# LPC_ERT_30_v3_51_RE.net
KiCad netlist of a schematic drawn in EAGLE
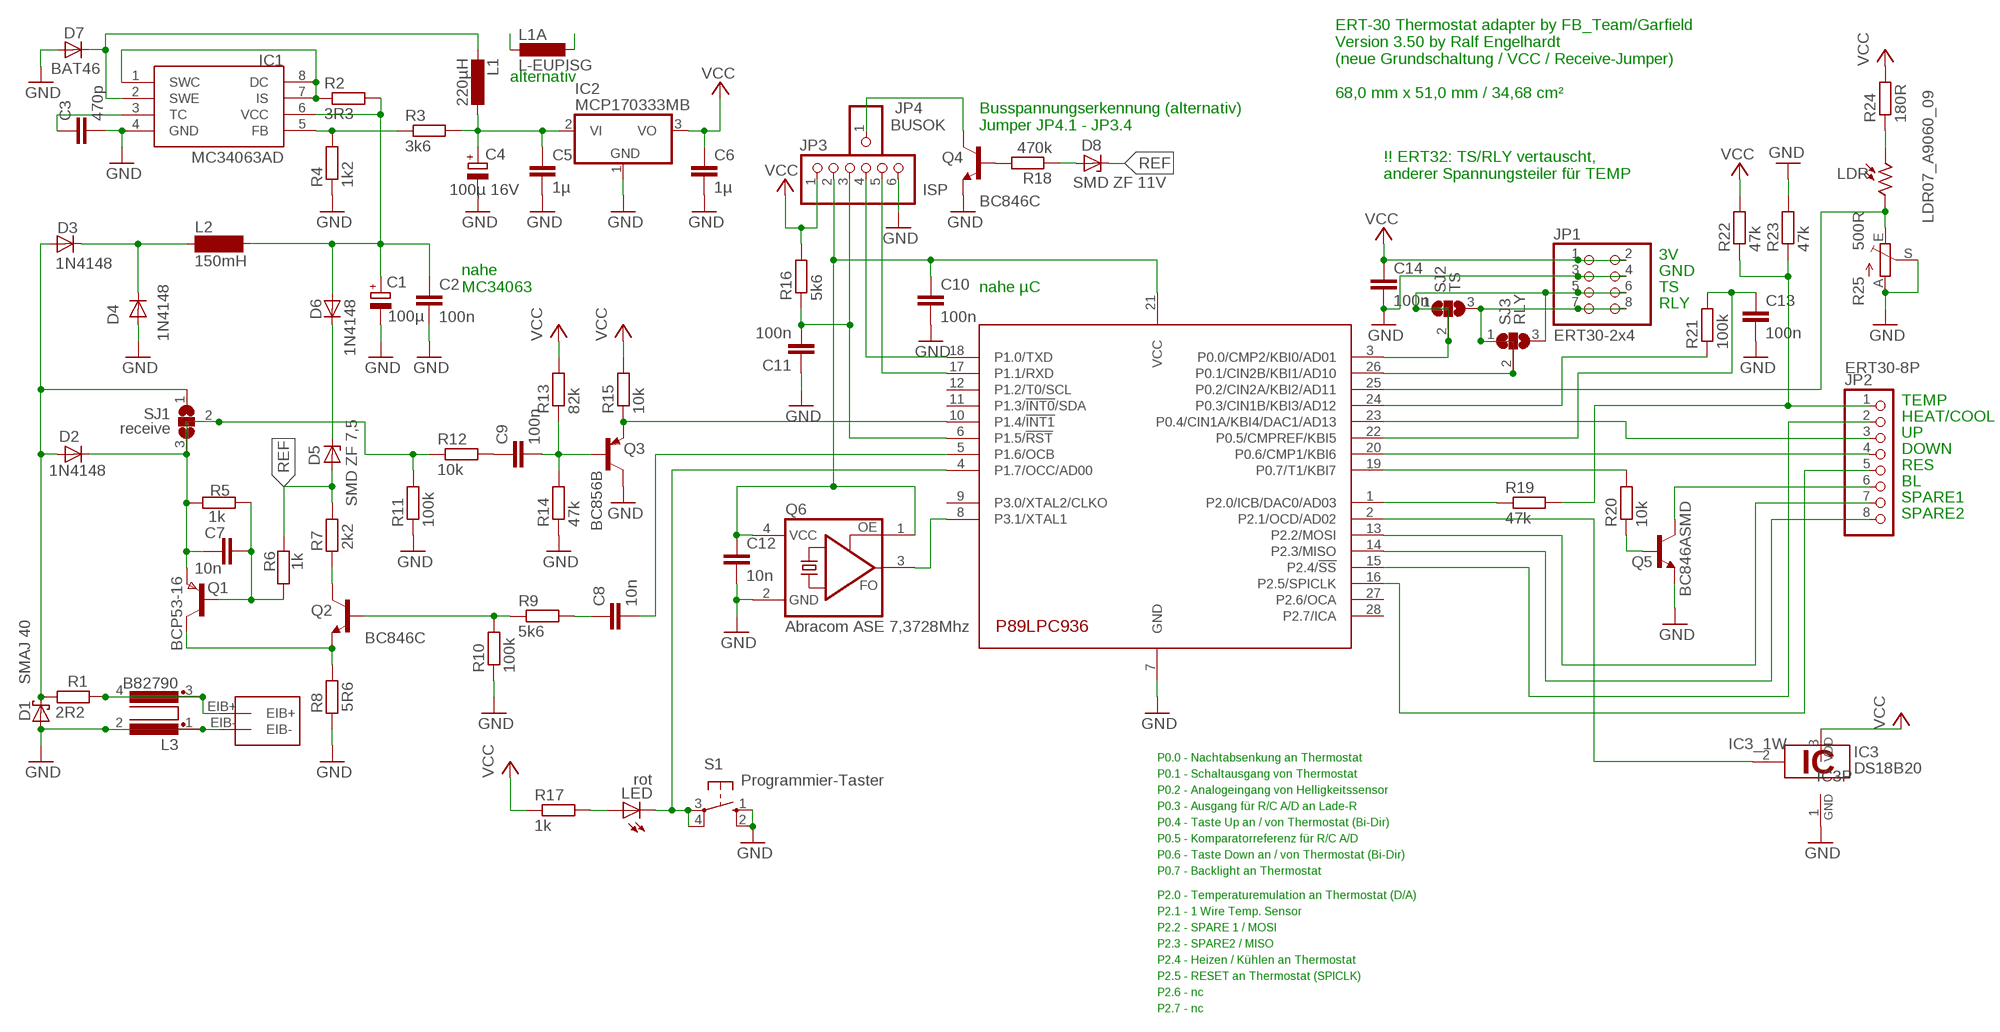
[diagram p0: schematic, sheet 1]

(export (version "E")
  (design (tool "Eeschema 10.0.6"))
  (components
    (comp (ref "C1")
      (value "100µ")
      (footprint "eagle-import:153CLV-0605")
      (libsource (lib "eagle-import") (part "CPOL-EU153CLV-0605"))
    )
    (comp (ref "C2")
      (value "100n")
      (footprint "eagle-import:C1206")
      (libsource (lib "eagle-import") (part "C-EUC1206"))
    )
    (comp (ref "C3")
      (value "470p")
      (footprint "eagle-import:C1206")
      (libsource (lib "eagle-import") (part "C-EUC1206"))
    )
    (comp (ref "C4")
      (value "100µ 16V")
      (footprint "eagle-import:153CLV-0605")
      (libsource (lib "eagle-import") (part "CPOL-EU153CLV-0605"))
    )
    (comp (ref "C5")
      (value "1µ")
      (footprint "eagle-import:C1206")
      (libsource (lib "eagle-import") (part "C-EUC1206"))
    )
    (comp (ref "C6")
      (value "1µ")
      (footprint "eagle-import:C1206")
      (libsource (lib "eagle-import") (part "C-EUC1206"))
    )
    (comp (ref "C7")
      (value "10n")
      (footprint "eagle-import:C1206")
      (libsource (lib "eagle-import") (part "C-EUC1206"))
    )
    (comp (ref "C8")
      (value "10n")
      (footprint "eagle-import:C1206")
      (libsource (lib "eagle-import") (part "C-EUC1206"))
    )
    (comp (ref "C9")
      (value "100n")
      (footprint "eagle-import:C1206")
      (libsource (lib "eagle-import") (part "C-EUC1206"))
    )
    (comp (ref "C10")
      (value "100n")
      (footprint "eagle-import:C1206")
      (libsource (lib "eagle-import") (part "C-EUC1206"))
    )
    (comp (ref "C11")
      (value "100n")
      (footprint "eagle-import:C1206")
      (libsource (lib "eagle-import") (part "C-EUC1206"))
    )
    (comp (ref "C12")
      (value "10n")
      (footprint "eagle-import:C1206")
      (libsource (lib "eagle-import") (part "C-EUC1206"))
    )
    (comp (ref "C13")
      (value "100n")
      (footprint "eagle-import:C1206")
      (libsource (lib "eagle-import") (part "C-EUC1206"))
    )
    (comp (ref "C14")
      (value "100n")
      (footprint "eagle-import:C1206")
      (libsource (lib "eagle-import") (part "C-EUC1206"))
    )
    (comp (ref "D1")
      (value "SMAJ 40")
      (footprint "eagle-import:SMB")
      (libsource (lib "eagle-import") (part "MBRS130LT3"))
    )
    (comp (ref "D2")
      (value "1N4148")
      (footprint "eagle-import:MINIMELF")
      (libsource (lib "eagle-import") (part "DIODE-MINIMELF"))
    )
    (comp (ref "D3")
      (value "1N4148")
      (footprint "eagle-import:MINIMELF")
      (libsource (lib "eagle-import") (part "DIODE-MINIMELF"))
    )
    (comp (ref "D4")
      (value "1N4148")
      (footprint "eagle-import:MINIMELF")
      (libsource (lib "eagle-import") (part "DIODE-MINIMELF"))
    )
    (comp (ref "D5")
      (value "SMD ZF 7,5")
      (footprint "eagle-import:MINIMELF")
      (libsource (lib "eagle-import") (part "ZENER-DIODESMD_ZF_XX"))
    )
    (comp (ref "D6")
      (value "1N4148")
      (footprint "eagle-import:MINIMELF")
      (libsource (lib "eagle-import") (part "DIODE-MINIMELF"))
    )
    (comp (ref "D7")
      (value "BAT46")
      (footprint "eagle-import:MINIMELF")
      (libsource (lib "eagle-import") (part "DIODE-MINIMELF"))
    )
    (comp (ref "D8")
      (value "SMD ZF 11V")
      (footprint "eagle-import:MINIMELF")
      (libsource (lib "eagle-import") (part "ZENER-DIODESMD_ZF_XX"))
    )
    (comp (ref "IC1")
      (value "MC34063AD")
      (footprint "eagle-import:SOIC8")
      (libsource (lib "eagle-import") (part "MC34063AD"))
    )
    (comp (ref "IC2")
      (value "MCP170333MB")
      (footprint "eagle-import:SOT89")
      (libsource (lib "eagle-import") (part "MCP1703MB33"))
    )
    (comp (ref "IC3")
      (value "DS18B20")
      (footprint "eagle-import:TO92-")
      (libsource (lib "eagle-import") (part "DS18B20"))
    )
    (comp (ref "JP1")
      (value "ERT30-2x4")
      (footprint "eagle-import:2X04")
      (libsource (lib "eagle-import") (part "PINHD-2X4"))
    )
    (comp (ref "JP2")
      (value "ERT30-8P")
      (footprint "eagle-import:PS-G-8")
      (libsource (lib "eagle-import") (part "PS-HEADER-8GERADE"))
    )
    (comp (ref "JP3")
      (value "ISP")
      (footprint "eagle-import:1X06_SELFBUS")
      (libsource (lib "eagle-import") (part "PINHD-1X6SELFBUS"))
    )
    (comp (ref "JP4")
      (value "BUSOK")
      (footprint "eagle-import:1X01_SELFBUS")
      (libsource (lib "eagle-import") (part "PINHD-1X1SELFBUS"))
    )
    (comp (ref "L1")
      (value "220µH")
      (footprint "eagle-import:PIS24XX")
      (libsource (lib "eagle-import") (part "L-EUPIS24XX"))
    )
    (comp (ref "L1A")
      (value "L-EUPISG")
      (footprint "eagle-import:PISG")
      (libsource (lib "eagle-import") (part "L-EUPISG"))
    )
    (comp (ref "L2")
      (value "150mH")
      (footprint "eagle-import:SD12_1000")
      (libsource (lib "eagle-import") (part "SD12-1000"))
    )
    (comp (ref "L3")
      (value "B82790")
      (footprint "eagle-import:B82790")
      (libsource (lib "eagle-import") (part "B82790"))
    )
    (comp (ref "LDR")
      (value "LDR07_A9060_09")
      (footprint "eagle-import:A90XX")
      (libsource (lib "eagle-import") (part "LDR07"))
    )
    (comp (ref "LED")
      (value "rot")
      (footprint "eagle-import:CHIPLED_1206")
      (libsource (lib "eagle-import") (part "LEDCHIPLED_1206"))
    )
    (comp (ref "LPC")
      (value "P98LPC936 TSOP28")
      (footprint "eagle-import:TSSOP28")
      (libsource (lib "eagle-import") (part "P89LPC936_SMDTSSOP28"))
    )
    (comp (ref "Q1")
      (value "BCP53-16")
      (footprint "eagle-import:SOT223")
      (fields (field (name "MPN") "DJT4030P-13"))
      (libsource (lib "eagle-import") (part "PNPSOT223"))
    )
    (comp (ref "Q2")
      (value "BC846C")
      (footprint "eagle-import:SOT23")
      (libsource (lib "eagle-import") (part "BC846"))
    )
    (comp (ref "Q3")
      (value "BC856B")
      (footprint "eagle-import:SOT23-BEC")
      (libsource (lib "eagle-import") (part "-PNP-SOT23-BECBC856B"))
    )
    (comp (ref "Q4")
      (value "BC846C")
      (footprint "eagle-import:SOT23")
      (libsource (lib "eagle-import") (part "BC846"))
    )
    (comp (ref "Q5")
      (value "BC846ASMD")
      (footprint "eagle-import:SOT23")
      (libsource (lib "eagle-import") (part "BC846SMDA"))
    )
    (comp (ref "Q6")
      (value "Abracom ASE 7,3728Mhz")
      (footprint "eagle-import:ASFL3")
      (libsource (lib "eagle-import") (part "ASFASFL3"))
    )
    (comp (ref "R1")
      (value "2R2")
      (footprint "eagle-import:R1206")
      (libsource (lib "eagle-import") (part "R-EU_R1206"))
    )
    (comp (ref "R2")
      (value "3R3")
      (footprint "eagle-import:R1206")
      (libsource (lib "eagle-import") (part "R-EU_R1206"))
    )
    (comp (ref "R3")
      (value "3k6")
      (footprint "eagle-import:R1206")
      (libsource (lib "eagle-import") (part "R-EU_R1206"))
    )
    (comp (ref "R4")
      (value "1k2")
      (footprint "eagle-import:R1206")
      (libsource (lib "eagle-import") (part "R-EU_R1206"))
    )
    (comp (ref "R5")
      (value "1k")
      (footprint "eagle-import:R1206")
      (libsource (lib "eagle-import") (part "R-EU_R1206"))
    )
    (comp (ref "R6")
      (value "1k")
      (footprint "eagle-import:R1206")
      (libsource (lib "eagle-import") (part "R-EU_R1206"))
    )
    (comp (ref "R7")
      (value "2k2")
      (footprint "eagle-import:R1206")
      (libsource (lib "eagle-import") (part "R-EU_R1206"))
    )
    (comp (ref "R8")
      (value "5R6")
      (footprint "eagle-import:R1206")
      (libsource (lib "eagle-import") (part "R-EU_R1206"))
    )
    (comp (ref "R9")
      (value "5k6")
      (footprint "eagle-import:R1206")
      (libsource (lib "eagle-import") (part "R-EU_R1206"))
    )
    (comp (ref "R10")
      (value "100k")
      (footprint "eagle-import:R1206")
      (libsource (lib "eagle-import") (part "R-EU_R1206"))
    )
    (comp (ref "R11")
      (value "100k")
      (footprint "eagle-import:R1206")
      (libsource (lib "eagle-import") (part "R-EU_R1206"))
    )
    (comp (ref "R12")
      (value "10k")
      (footprint "eagle-import:R1206")
      (libsource (lib "eagle-import") (part "R-EU_R1206"))
    )
    (comp (ref "R13")
      (value "82k")
      (footprint "eagle-import:R1206")
      (libsource (lib "eagle-import") (part "R-EU_R1206"))
    )
    (comp (ref "R14")
      (value "47k")
      (footprint "eagle-import:R1206")
      (libsource (lib "eagle-import") (part "R-EU_R1206"))
    )
    (comp (ref "R15")
      (value "10k")
      (footprint "eagle-import:R1206")
      (libsource (lib "eagle-import") (part "R-EU_R1206"))
    )
    (comp (ref "R16")
      (value "5k6")
      (footprint "eagle-import:R1206")
      (libsource (lib "eagle-import") (part "R-EU_R1206"))
    )
    (comp (ref "R17")
      (value "1k")
      (footprint "eagle-import:R1206")
      (libsource (lib "eagle-import") (part "R-EU_R1206"))
    )
    (comp (ref "R18")
      (value "470k")
      (footprint "eagle-import:R1206")
      (libsource (lib "eagle-import") (part "R-EU_R1206"))
    )
    (comp (ref "R19")
      (value "47k")
      (footprint "eagle-import:R1206")
      (libsource (lib "eagle-import") (part "R-EU_R1206"))
    )
    (comp (ref "R20")
      (value "10k")
      (footprint "eagle-import:R1206")
      (libsource (lib "eagle-import") (part "R-EU_R1206"))
    )
    (comp (ref "R21")
      (value "100k")
      (footprint "eagle-import:R1206")
      (libsource (lib "eagle-import") (part "R-EU_R1206"))
    )
    (comp (ref "R22")
      (value "47k")
      (footprint "eagle-import:R1206")
      (libsource (lib "eagle-import") (part "R-EU_R1206"))
    )
    (comp (ref "R23")
      (value "47k")
      (footprint "eagle-import:R1206")
      (libsource (lib "eagle-import") (part "R-EU_R1206"))
    )
    (comp (ref "R24")
      (value "180R")
      (footprint "eagle-import:R1206")
      (libsource (lib "eagle-import") (part "R-EU_R1206"))
    )
    (comp (ref "R25")
      (value "500R")
      (footprint "eagle-import:CA6H")
      (libsource (lib "eagle-import") (part "TRIM_EU-CA6H"))
    )
    (comp (ref "S1")
      (value "Programmier-Taster")
      (footprint "eagle-import:B3F-10XX")
      (fields (field (name "MPN") "B3F-1000"))
      (libsource (lib "eagle-import") (part "10-XX"))
    )
    (comp (ref "SJ1")
      (value "receive")
      (footprint "eagle-import:SJ_2")
      (libsource (lib "eagle-import") (part "SJ2W"))
    )
    (comp (ref "SJ2")
      (value "TS")
      (footprint "eagle-import:SJ_2")
      (libsource (lib "eagle-import") (part "SJ2W"))
    )
    (comp (ref "SJ3")
      (value "RLY")
      (footprint "eagle-import:SJ_2")
      (libsource (lib "eagle-import") (part "SJ2W"))
    )
    (comp (ref "U$5")
      (value "EIB-CON")
      (footprint "eagle-import:EIB-CON")
      (libsource (lib "eagle-import") (part "EIB-CON"))
    )
  )
  (nets
    (net (code "1") (name "/+5V") (class "Default")
      (node (ref "C4") (pin "+") (pinfunction "+_+") (pintype "passive"))
      (node (ref "C5") (pin "1") (pinfunction "1_1") (pintype "passive"))
      (node (ref "IC2") (pin "2") (pinfunction "VI_2") (pintype "input"))
      (node (ref "IC2") (pin "2@1") (pinfunction "VI1_2@1") (pintype "input"))
      (node (ref "L1") (pin "2") (pinfunction "1_2") (pintype "passive"))
      (node (ref "L1A") (pin "2") (pinfunction "2_2") (pintype "passive"))
      (node (ref "R3") (pin "2") (pinfunction "2_2") (pintype "passive"))
    )
    (net (code "2") (name "/SWE") (class "Default")
      (node (ref "D7") (pin "C") (pinfunction "C_C") (pintype "passive"))
      (node (ref "IC1") (pin "2") (pinfunction "SWE_2") (pintype "passive"))
      (node (ref "L1") (pin "1") (pinfunction "2_1") (pintype "passive"))
      (node (ref "L1A") (pin "1") (pinfunction "1_1") (pintype "passive"))
    )
    (net (code "3") (name "GND") (class "Default")
      (node (ref "C1") (pin "-") (pinfunction "-_-") (pintype "passive"))
      (node (ref "C10") (pin "2") (pinfunction "2_2") (pintype "passive"))
      (node (ref "C11") (pin "1") (pinfunction "1_1") (pintype "passive"))
      (node (ref "C12") (pin "2") (pinfunction "2_2") (pintype "passive"))
      (node (ref "C13") (pin "2") (pinfunction "2_2") (pintype "passive"))
      (node (ref "C14") (pin "2") (pinfunction "2_2") (pintype "passive"))
      (node (ref "C2") (pin "2") (pinfunction "2_2") (pintype "passive"))
      (node (ref "C3") (pin "2") (pinfunction "2_2") (pintype "passive"))
      (node (ref "C4") (pin "-") (pinfunction "-_-") (pintype "passive"))
      (node (ref "C5") (pin "2") (pinfunction "2_2") (pintype "passive"))
      (node (ref "C6") (pin "2") (pinfunction "2_2") (pintype "passive"))
      (node (ref "D1") (pin "A") (pinfunction "A_A") (pintype "passive"))
      (node (ref "D4") (pin "A") (pinfunction "A_A") (pintype "passive"))
      (node (ref "D7") (pin "A") (pinfunction "A_A") (pintype "passive"))
      (node (ref "IC1") (pin "4") (pinfunction "GND_4") (pintype "passive"))
      (node (ref "IC2") (pin "1") (pinfunction "GND_1") (pintype "passive"))
      (node (ref "IC3") (pin "1") (pinfunction "GND_1") (pintype "power_in"))
      (node (ref "JP1") (pin "3") (pinfunction "3_3") (pintype "passive"))
      (node (ref "JP1") (pin "4") (pinfunction "4_4") (pintype "passive"))
      (node (ref "JP3") (pin "6") (pinfunction "6_6") (pintype "passive"))
      (node (ref "L3") (pin "1") (pinfunction "1_1") (pintype "passive"))
      (node (ref "L3") (pin "2") (pinfunction "2_2") (pintype "passive"))
      (node (ref "LPC") (pin "7") (pinfunction "GND_7") (pintype "bidirectional"))
      (node (ref "Q3") (pin "C") (pinfunction "C_C") (pintype "passive"))
      (node (ref "Q4") (pin "2") (pinfunction "E_2") (pintype "passive"))
      (node (ref "Q5") (pin "2") (pinfunction "E_2") (pintype "passive"))
      (node (ref "Q6") (pin "2") (pinfunction "GND_2") (pintype "power_in"))
      (node (ref "R10") (pin "1") (pinfunction "1_1") (pintype "passive"))
      (node (ref "R11") (pin "1") (pinfunction "1_1") (pintype "passive"))
      (node (ref "R14") (pin "1") (pinfunction "1_1") (pintype "passive"))
      (node (ref "R23") (pin "2") (pinfunction "2_2") (pintype "passive"))
      (node (ref "R25") (pin "A") (pinfunction "A_A") (pintype "passive"))
      (node (ref "R25") (pin "S") (pinfunction "S_S") (pintype "passive"))
      (node (ref "R4") (pin "1") (pinfunction "1_1") (pintype "passive"))
      (node (ref "R8") (pin "1") (pinfunction "1_1") (pintype "passive"))
      (node (ref "S1") (pin "1") (pinfunction "S_1") (pintype "passive"))
      (node (ref "S1") (pin "2") (pinfunction "S1_2") (pintype "passive"))
      (node (ref "U$5") (pin "EIB-") (pinfunction "EIB-_EIB-") (pintype "bidirectional"))
    )
    (net (code "4") (name "Net-(C8-Pad1)") (class "Default")
      (node (ref "C8") (pin "1") (pinfunction "1_1") (pintype "passive"))
      (node (ref "R9") (pin "2") (pinfunction "2_2") (pintype "passive"))
    )
    (net (code "5") (name "Net-(C9-Pad1)") (class "Default")
      (node (ref "C9") (pin "1") (pinfunction "1_1") (pintype "passive"))
      (node (ref "R12") (pin "2") (pinfunction "2_2") (pintype "passive"))
    )
    (net (code "6") (name "Net-(C9-Pad2)") (class "Default")
      (node (ref "C9") (pin "2") (pinfunction "2_2") (pintype "passive"))
      (node (ref "Q3") (pin "B") (pinfunction "B_B") (pintype "passive"))
      (node (ref "R13") (pin "1") (pinfunction "1_1") (pintype "passive"))
      (node (ref "R14") (pin "2") (pinfunction "2_2") (pintype "passive"))
    )
    (net (code "7") (name "Net-(D1-PadC)") (class "Default")
      (node (ref "D1") (pin "C") (pinfunction "C_C") (pintype "passive"))
      (node (ref "D2") (pin "A") (pinfunction "A_A") (pintype "passive"))
      (node (ref "D3") (pin "A") (pinfunction "A_A") (pintype "passive"))
      (node (ref "R1") (pin "2") (pinfunction "2_2") (pintype "passive"))
      (node (ref "SJ1") (pin "1") (pinfunction "1_1") (pintype "passive"))
    )
    (net (code "8") (name "Net-(D3-PadC)") (class "Default")
      (node (ref "D3") (pin "C") (pinfunction "C_C") (pintype "passive"))
      (node (ref "D4") (pin "C") (pinfunction "C_C") (pintype "passive"))
      (node (ref "L2") (pin "1") (pinfunction "1_1") (pintype "passive"))
    )
    (net (code "9") (name "Net-(D5-PadC)") (class "Default")
      (node (ref "D5") (pin "C") (pinfunction "C_C") (pintype "passive"))
      (node (ref "D6") (pin "C") (pinfunction "C_C") (pintype "passive"))
    )
    (net (code "10") (name "Net-(D8-PadA)") (class "Default")
      (node (ref "D8") (pin "A") (pinfunction "A_A") (pintype "passive"))
      (node (ref "R18") (pin "1") (pinfunction "1_1") (pintype "passive"))
    )
    (net (code "11") (name "Net-(IC1-DC)") (class "Default")
      (node (ref "IC1") (pin "1") (pinfunction "SWC_1") (pintype "passive"))
      (node (ref "IC1") (pin "7") (pinfunction "IS_7") (pintype "passive"))
      (node (ref "IC1") (pin "8") (pinfunction "DC_8") (pintype "passive"))
      (node (ref "R2") (pin "1") (pinfunction "1_1") (pintype "passive"))
    )
    (net (code "12") (name "Net-(IC1-FB)") (class "Default")
      (node (ref "IC1") (pin "5") (pinfunction "FB_5") (pintype "passive"))
      (node (ref "R3") (pin "1") (pinfunction "1_1") (pintype "passive"))
      (node (ref "R4") (pin "2") (pinfunction "2_2") (pintype "passive"))
    )
    (net (code "13") (name "Net-(IC1-TC)") (class "Default")
      (node (ref "C3") (pin "1") (pinfunction "1_1") (pintype "passive"))
      (node (ref "IC1") (pin "3") (pinfunction "TC_3") (pintype "passive"))
    )
    (net (code "14") (name "Net-(IC1-VCC)") (class "Default")
      (node (ref "C1") (pin "+") (pinfunction "+_+") (pintype "passive"))
      (node (ref "C2") (pin "1") (pinfunction "1_1") (pintype "passive"))
      (node (ref "D6") (pin "A") (pinfunction "A_A") (pintype "passive"))
      (node (ref "IC1") (pin "6") (pinfunction "VCC_6") (pintype "passive"))
      (node (ref "L2") (pin "2") (pinfunction "2_2") (pintype "passive"))
      (node (ref "R2") (pin "2") (pinfunction "2_2") (pintype "passive"))
    )
    (net (code "15") (name "Net-(IC3C-1W)") (class "Default")
      (node (ref "IC3") (pin "2") (pinfunction "1W_2") (pintype "power_in"))
      (node (ref "LPC") (pin "2") (pinfunction "P2.1/OCD/AD02_2") (pintype "bidirectional"))
    )
    (net (code "16") (name "Net-(JP2-Pad1)") (class "Default")
      (node (ref "JP2") (pin "1") (pinfunction "1_1") (pintype "passive"))
      (node (ref "R19") (pin "2") (pinfunction "2_2") (pintype "passive"))
      (node (ref "R22") (pin "1") (pinfunction "1_1") (pintype "passive"))
      (node (ref "R23") (pin "1") (pinfunction "1_1") (pintype "passive"))
    )
    (net (code "17") (name "Net-(L3-Pad3)") (class "Default")
      (node (ref "L3") (pin "3") (pinfunction "3_3") (pintype "passive"))
      (node (ref "L3") (pin "4") (pinfunction "4_4") (pintype "passive"))
      (node (ref "R1") (pin "1") (pinfunction "1_1") (pintype "passive"))
      (node (ref "U$5") (pin "EIB+") (pinfunction "EIB+_EIB+") (pintype "bidirectional"))
    )
    (net (code "18") (name "Net-(LDR-1)") (class "Default")
      (node (ref "LDR") (pin "P$1") (pinfunction "1_P$1") (pintype "passive"))
      (node (ref "R24") (pin "1") (pinfunction "1_1") (pintype "passive"))
    )
    (net (code "19") (name "Net-(LDR-2)") (class "Default")
      (node (ref "LDR") (pin "P$2") (pinfunction "2_P$2") (pintype "passive"))
      (node (ref "LPC") (pin "25") (pinfunction "P0.2/CIN2A/KBI2/AD11_25") (pintype "bidirectional"))
      (node (ref "R25") (pin "E") (pinfunction "E_E") (pintype "passive"))
    )
    (net (code "20") (name "Net-(LED-PadA)") (class "Default")
      (node (ref "LED") (pin "A") (pinfunction "A_A") (pintype "passive"))
      (node (ref "R17") (pin "2") (pinfunction "2_2") (pintype "passive"))
    )
    (net (code "21") (name "Net-(LPC-P0.0{slash}CMP2{slash}KBI0{slash}AD01)") (class "Default")
      (node (ref "JP1") (pin "5") (pinfunction "5_5") (pintype "passive"))
      (node (ref "JP1") (pin "6") (pinfunction "6_6") (pintype "passive"))
      (node (ref "LPC") (pin "3") (pinfunction "P0.0/CMP2/KBI0/AD01_3") (pintype "bidirectional"))
      (node (ref "SJ2") (pin "1") (pinfunction "1_1") (pintype "passive"))
      (node (ref "SJ2") (pin "2") (pinfunction "2_2") (pintype "passive"))
      (node (ref "SJ3") (pin "3") (pinfunction "3_3") (pintype "passive"))
    )
    (net (code "22") (name "Net-(LPC-P0.1{slash}CIN2B{slash}KBI1{slash}AD10)") (class "Default")
      (node (ref "JP1") (pin "7") (pinfunction "7_7") (pintype "passive"))
      (node (ref "JP1") (pin "8") (pinfunction "8_8") (pintype "passive"))
      (node (ref "LPC") (pin "26") (pinfunction "P0.1/CIN2B/KBI1/AD10_26") (pintype "bidirectional"))
      (node (ref "SJ2") (pin "3") (pinfunction "3_3") (pintype "passive"))
      (node (ref "SJ3") (pin "1") (pinfunction "1_1") (pintype "passive"))
      (node (ref "SJ3") (pin "2") (pinfunction "2_2") (pintype "passive"))
    )
    (net (code "23") (name "Net-(LPC-P0.3{slash}CIN1B{slash}KBI3{slash}AD12)") (class "Default")
      (node (ref "LPC") (pin "24") (pinfunction "P0.3/CIN1B/KBI3/AD12_24") (pintype "bidirectional"))
      (node (ref "R21") (pin "1") (pinfunction "1_1") (pintype "passive"))
    )
    (net (code "24") (name "Net-(LPC-P0.4{slash}CIN1A{slash}KBI4{slash}DAC1{slash}AD13)") (class "Default")
      (node (ref "JP2") (pin "3") (pinfunction "3_3") (pintype "passive"))
      (node (ref "LPC") (pin "23") (pinfunction "P0.4/CIN1A/KBI4/DAC1/AD13_23") (pintype "bidirectional"))
    )
    (net (code "25") (name "Net-(LPC-P0.5{slash}CMPREF{slash}KBI5)") (class "Default")
      (node (ref "C13") (pin "1") (pinfunction "1_1") (pintype "passive"))
      (node (ref "LPC") (pin "22") (pinfunction "P0.5/CMPREF/KBI5_22") (pintype "bidirectional"))
      (node (ref "R21") (pin "2") (pinfunction "2_2") (pintype "passive"))
    )
    (net (code "26") (name "Net-(LPC-P0.6{slash}CMP1{slash}KBI6)") (class "Default")
      (node (ref "JP2") (pin "4") (pinfunction "4_4") (pintype "passive"))
      (node (ref "LPC") (pin "20") (pinfunction "P0.6/CMP1/KBI6_20") (pintype "bidirectional"))
    )
    (net (code "27") (name "Net-(LPC-P0.7{slash}T1{slash}KBI7)") (class "Default")
      (node (ref "LPC") (pin "19") (pinfunction "P0.7/T1/KBI7_19") (pintype "bidirectional"))
      (node (ref "R20") (pin "2") (pinfunction "2_2") (pintype "passive"))
    )
    (net (code "28") (name "Net-(LPC-P1.0{slash}TXD)") (class "Default")
      (node (ref "JP3") (pin "4") (pinfunction "4_4") (pintype "passive"))
      (node (ref "LPC") (pin "18") (pinfunction "P1.0/TXD_18") (pintype "bidirectional"))
    )
    (net (code "29") (name "Net-(LPC-P1.1{slash}RXD)") (class "Default")
      (node (ref "JP3") (pin "5") (pinfunction "5_5") (pintype "passive"))
      (node (ref "LPC") (pin "17") (pinfunction "P1.1/RXD_17") (pintype "bidirectional"))
    )
    (net (code "30") (name "Net-(LPC-P1.4{slash}~{INT1})") (class "Default")
      (node (ref "LPC") (pin "10") (pinfunction "P1.4/~{INT1}_10") (pintype "bidirectional"))
      (node (ref "Q3") (pin "E") (pinfunction "E_E") (pintype "passive"))
      (node (ref "R15") (pin "1") (pinfunction "1_1") (pintype "passive"))
    )
    (net (code "31") (name "Net-(LPC-P1.5{slash}~{RST})") (class "Default")
      (node (ref "C11") (pin "2") (pinfunction "2_2") (pintype "passive"))
      (node (ref "JP3") (pin "3") (pinfunction "3_3") (pintype "passive"))
      (node (ref "LPC") (pin "6") (pinfunction "P1.5/~{RST}_6") (pintype "bidirectional"))
      (node (ref "R16") (pin "1") (pinfunction "1_1") (pintype "passive"))
    )
    (net (code "32") (name "Net-(LPC-P1.6{slash}OCB)") (class "Default")
      (node (ref "C8") (pin "2") (pinfunction "2_2") (pintype "passive"))
      (node (ref "LPC") (pin "5") (pinfunction "P1.6/OCB_5") (pintype "bidirectional"))
    )
    (net (code "33") (name "Net-(LPC-P1.7{slash}OCC{slash}AD00)") (class "Default")
      (node (ref "LED") (pin "C") (pinfunction "C_C") (pintype "passive"))
      (node (ref "LPC") (pin "4") (pinfunction "P1.7/OCC/AD00_4") (pintype "bidirectional"))
      (node (ref "S1") (pin "3") (pinfunction "P_3") (pintype "passive"))
      (node (ref "S1") (pin "4") (pinfunction "P1_4") (pintype "passive"))
    )
    (net (code "34") (name "Net-(LPC-P2.0{slash}ICB{slash}DAC0{slash}AD03)") (class "Default")
      (node (ref "LPC") (pin "1") (pinfunction "P2.0/ICB/DAC0/AD03_1") (pintype "bidirectional"))
      (node (ref "R19") (pin "1") (pinfunction "1_1") (pintype "passive"))
    )
    (net (code "35") (name "Net-(LPC-P2.2{slash}MOSI)") (class "Default")
      (node (ref "JP2") (pin "7") (pinfunction "7_7") (pintype "passive"))
      (node (ref "LPC") (pin "13") (pinfunction "P2.2/MOSI_13") (pintype "bidirectional"))
    )
    (net (code "36") (name "Net-(LPC-P2.3{slash}MISO)") (class "Default")
      (node (ref "JP2") (pin "8") (pinfunction "8_8") (pintype "passive"))
      (node (ref "LPC") (pin "14") (pinfunction "P2.3/MISO_14") (pintype "bidirectional"))
    )
    (net (code "37") (name "Net-(LPC-P2.4{slash}~{SS})") (class "Default")
      (node (ref "JP2") (pin "2") (pinfunction "2_2") (pintype "passive"))
      (node (ref "LPC") (pin "15") (pinfunction "P2.4/~{SS}_15") (pintype "bidirectional"))
    )
    (net (code "38") (name "Net-(LPC-P2.5{slash}SPICLK)") (class "Default")
      (node (ref "JP2") (pin "5") (pinfunction "5_5") (pintype "passive"))
      (node (ref "LPC") (pin "16") (pinfunction "P2.5/SPICLK_16") (pintype "bidirectional"))
    )
    (net (code "39") (name "Net-(LPC-P3.1{slash}XTAL1)") (class "Default")
      (node (ref "LPC") (pin "8") (pinfunction "P3.1/XTAL1_8") (pintype "bidirectional"))
      (node (ref "Q6") (pin "3") (pinfunction "FO_3") (pintype "output"))
    )
    (net (code "40") (name "Net-(LPC-VCC)") (class "Default")
      (node (ref "C10") (pin "1") (pinfunction "1_1") (pintype "passive"))
      (node (ref "C12") (pin "1") (pinfunction "1_1") (pintype "passive"))
      (node (ref "JP3") (pin "2") (pinfunction "2_2") (pintype "passive"))
      (node (ref "LPC") (pin "21") (pinfunction "VCC_21") (pintype "bidirectional"))
      (node (ref "Q6") (pin "1") (pinfunction "OE_1") (pintype "input"))
      (node (ref "Q6") (pin "4") (pinfunction "VCC_4") (pintype "power_in"))
    )
    (net (code "41") (name "Net-(Q1-B)") (class "Default")
      (node (ref "C7") (pin "1") (pinfunction "1_1") (pintype "passive"))
      (node (ref "Q1") (pin "1") (pinfunction "B_1") (pintype "passive"))
      (node (ref "R5") (pin "1") (pinfunction "1_1") (pintype "passive"))
      (node (ref "R6") (pin "2") (pinfunction "2_2") (pintype "passive"))
    )
    (net (code "42") (name "Net-(Q1-E)") (class "Default")
      (node (ref "C7") (pin "2") (pinfunction "2_2") (pintype "passive"))
      (node (ref "D2") (pin "C") (pinfunction "C_C") (pintype "passive"))
      (node (ref "Q1") (pin "3") (pinfunction "E_3") (pintype "passive"))
      (node (ref "R11") (pin "2") (pinfunction "2_2") (pintype "passive"))
      (node (ref "R12") (pin "1") (pinfunction "1_1") (pintype "passive"))
      (node (ref "R5") (pin "2") (pinfunction "2_2") (pintype "passive"))
      (node (ref "SJ1") (pin "2") (pinfunction "2_2") (pintype "passive"))
      (node (ref "SJ1") (pin "3") (pinfunction "3_3") (pintype "passive"))
    )
    (net (code "43") (name "Net-(Q2-B)") (class "Default")
      (node (ref "Q2") (pin "1") (pinfunction "B_1") (pintype "passive"))
      (node (ref "R10") (pin "2") (pinfunction "2_2") (pintype "passive"))
      (node (ref "R9") (pin "1") (pinfunction "1_1") (pintype "passive"))
    )
    (net (code "44") (name "Net-(Q2-C)") (class "Default")
      (node (ref "Q2") (pin "3") (pinfunction "C_3") (pintype "passive"))
      (node (ref "R7") (pin "1") (pinfunction "1_1") (pintype "passive"))
    )
    (net (code "45") (name "Net-(Q2-E)") (class "Default")
      (node (ref "Q1") (pin "2") (pinfunction "C_2") (pintype "passive"))
      (node (ref "Q1") (pin "4") (pinfunction "C_4") (pintype "passive"))
      (node (ref "Q2") (pin "2") (pinfunction "E_2") (pintype "passive"))
      (node (ref "R8") (pin "2") (pinfunction "2_2") (pintype "passive"))
    )
    (net (code "46") (name "Net-(Q4-B)") (class "Default")
      (node (ref "Q4") (pin "1") (pinfunction "B_1") (pintype "passive"))
      (node (ref "R18") (pin "2") (pinfunction "2_2") (pintype "passive"))
    )
    (net (code "47") (name "Net-(Q4-C)") (class "Default")
      (node (ref "JP4") (pin "1") (pinfunction "1_1") (pintype "passive"))
      (node (ref "Q4") (pin "3") (pinfunction "C_3") (pintype "passive"))
    )
    (net (code "48") (name "Net-(Q5-B)") (class "Default")
      (node (ref "Q5") (pin "1") (pinfunction "B_1") (pintype "passive"))
      (node (ref "R20") (pin "1") (pinfunction "1_1") (pintype "passive"))
    )
    (net (code "49") (name "Net-(Q5-C)") (class "Default")
      (node (ref "JP2") (pin "6") (pinfunction "6_6") (pintype "passive"))
      (node (ref "Q5") (pin "3") (pinfunction "C_3") (pintype "passive"))
    )
    (net (code "50") (name "REF") (class "Default")
      (node (ref "D5") (pin "A") (pinfunction "A_A") (pintype "passive"))
      (node (ref "D8") (pin "C") (pinfunction "C_C") (pintype "passive"))
      (node (ref "R6") (pin "1") (pinfunction "1_1") (pintype "passive"))
      (node (ref "R7") (pin "2") (pinfunction "2_2") (pintype "passive"))
    )
    (net (code "51") (name "VCC") (class "Default")
      (node (ref "C14") (pin "1") (pinfunction "1_1") (pintype "passive"))
      (node (ref "C6") (pin "1") (pinfunction "1_1") (pintype "passive"))
      (node (ref "IC2") (pin "3") (pinfunction "VO_3") (pintype "passive"))
      (node (ref "IC3") (pin "3") (pinfunction "VDD_3") (pintype "power_in"))
      (node (ref "JP1") (pin "1") (pinfunction "1_1") (pintype "passive"))
      (node (ref "JP1") (pin "2") (pinfunction "2_2") (pintype "passive"))
      (node (ref "JP3") (pin "1") (pinfunction "1_1") (pintype "passive"))
      (node (ref "R13") (pin "2") (pinfunction "2_2") (pintype "passive"))
      (node (ref "R15") (pin "2") (pinfunction "2_2") (pintype "passive"))
      (node (ref "R16") (pin "2") (pinfunction "2_2") (pintype "passive"))
      (node (ref "R17") (pin "1") (pinfunction "1_1") (pintype "passive"))
      (node (ref "R22") (pin "2") (pinfunction "2_2") (pintype "passive"))
      (node (ref "R24") (pin "2") (pinfunction "2_2") (pintype "passive"))
    )
    (net (code "52") (name "unconnected-(LPC-P1.2{slash}T0{slash}SCL-Pad12)") (class "Default")
      (node (ref "LPC") (pin "12") (pinfunction "P1.2/T0/SCL_12") (pintype "bidirectional"))
    )
    (net (code "53") (name "unconnected-(LPC-P1.3{slash}~{INT0}{slash}SDA-Pad11)") (class "Default")
      (node (ref "LPC") (pin "11") (pinfunction "P1.3/~{INT0}/SDA_11") (pintype "bidirectional"))
    )
    (net (code "54") (name "unconnected-(LPC-P2.6{slash}OCA-Pad27)") (class "Default")
      (node (ref "LPC") (pin "27") (pinfunction "P2.6/OCA_27") (pintype "bidirectional"))
    )
    (net (code "55") (name "unconnected-(LPC-P2.7{slash}ICA-Pad28)") (class "Default")
      (node (ref "LPC") (pin "28") (pinfunction "P2.7/ICA_28") (pintype "bidirectional"))
    )
    (net (code "56") (name "unconnected-(LPC-P3.0{slash}XTAL2{slash}CLKO-Pad9)") (class "Default")
      (node (ref "LPC") (pin "9") (pinfunction "P3.0/XTAL2/CLKO_9") (pintype "bidirectional"))
    )
  )
)
